# ZYNQ400-DDR.net
KiCad netlist of a schematic drawn in Altium Designer
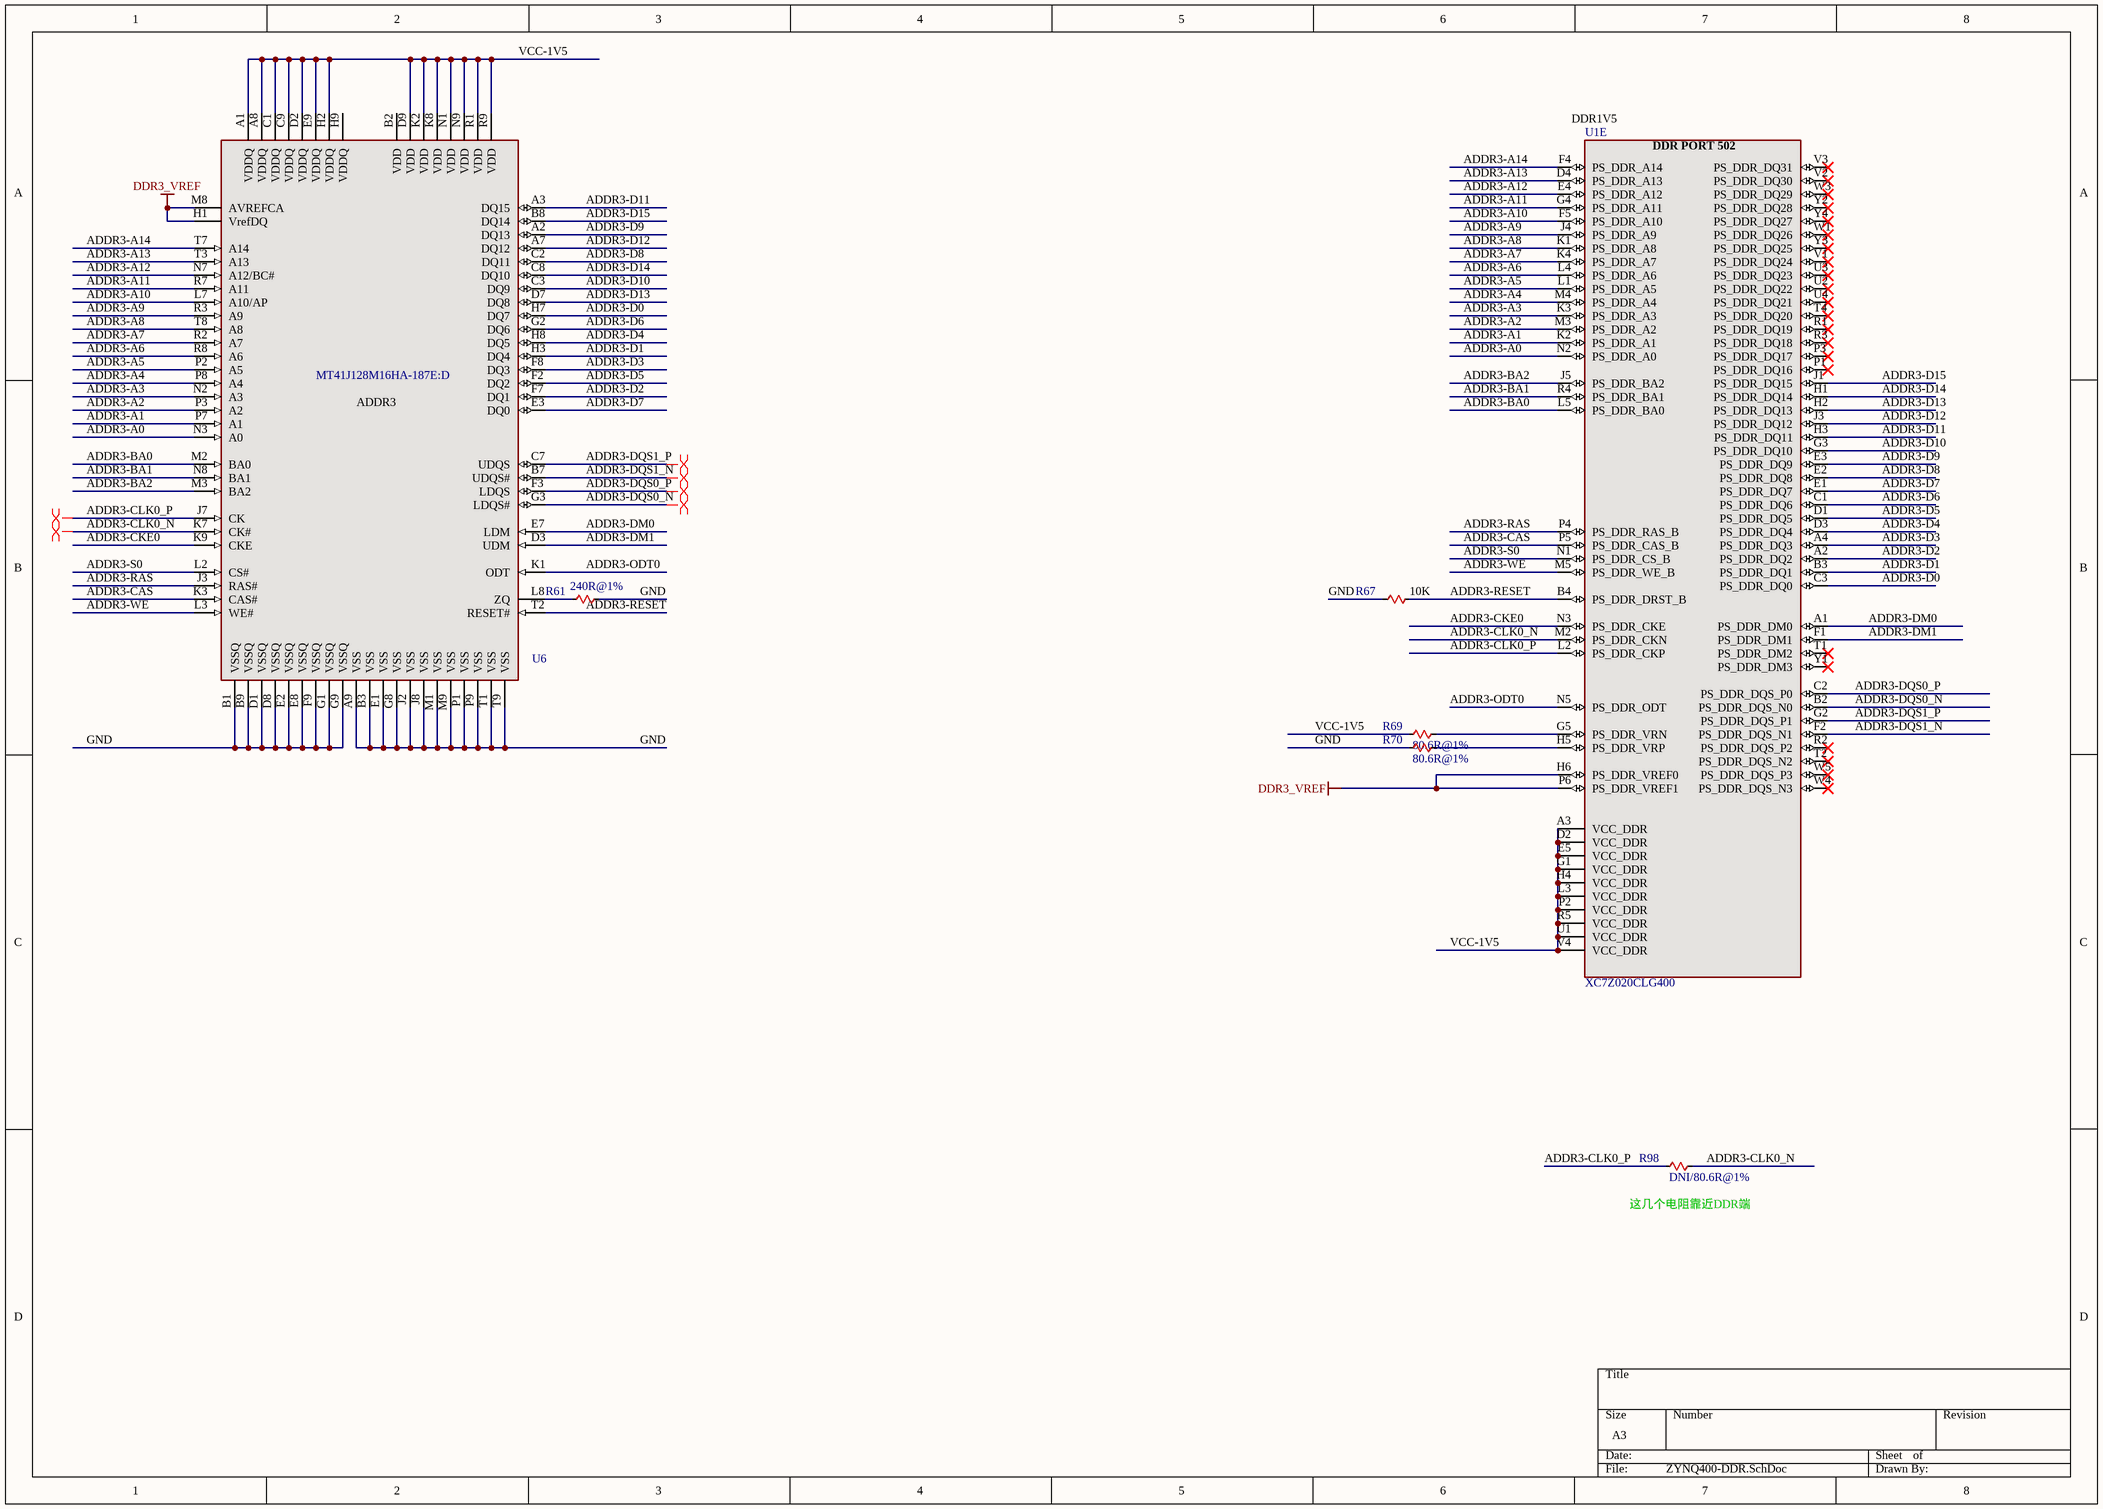
[diagram p0: ZYNQ400-DDR.SchDoc]

(export (version "E")
  (design (tool "Eeschema 10.0.6"))
  (components
    (comp (ref "R61")
      (value "240R@1%")
      (footprint "0402")
      (description "Generic Resistor")
      (libsource (lib "Digilent") (part "RESISTOR"))
    )
    (comp (ref "R67")
      (value "10K")
      (footprint "0402")
      (description "Generic Resistor")
      (libsource (lib "Digilent") (part "RESISTOR"))
    )
    (comp (ref "R69")
      (value "80.6R@1%")
      (footprint "0402")
      (description "Generic Resistor")
      (libsource (lib "Digilent") (part "RESISTOR"))
    )
    (comp (ref "R70")
      (value "80.6R@1%")
      (footprint "0402")
      (description "Generic Resistor")
      (libsource (lib "Digilent") (part "RESISTOR"))
    )
    (comp (ref "R98")
      (value "DNI/80.6R@1%")
      (footprint "0402")
      (description "Generic Resistor")
      (libsource (lib "Digilent") (part "RESISTOR"))
    )
    (comp (ref "U1")
      (value "XC7Z020CLG400")
      (footprint "CLG400")
      (description "Zynq 7000 FPGA 20 Die, in a CSG 484 Package")
      (fields (field (name "MANUFACTURER") "Xilinx"))
      (libsource (lib "gjws") (part "XC7Z020-CLG400"))
    )
    (comp (ref "U6")
      (value "MT41J128M16HA-187E:D")
      (footprint "FBGA96")
      (description "DDR3 SDRAM 2Gb x4, x8, x16")
      (fields (field (name "MANUFACTURER") "Micron"))
      (libsource (lib "Digilent") (part "MT41JxxxMxx"))
    )
  )
  (nets
    (net (code "1") (name "/ADDR3-A0") (class "Default")
      (node (ref "U1") (pin "N2") (pinfunction "PS_DDR_A0_N2") (pintype "bidirectional"))
      (node (ref "U6") (pin "N3") (pinfunction "A0_N3") (pintype "input"))
    )
    (net (code "2") (name "/ADDR3-A1") (class "Default")
      (node (ref "U1") (pin "K2") (pinfunction "PS_DDR_A1_K2") (pintype "bidirectional"))
      (node (ref "U6") (pin "P7") (pinfunction "A1_P7") (pintype "input"))
    )
    (net (code "3") (name "/ADDR3-A2") (class "Default")
      (node (ref "U1") (pin "M3") (pinfunction "PS_DDR_A2_M3") (pintype "bidirectional"))
      (node (ref "U6") (pin "P3") (pinfunction "A2_P3") (pintype "input"))
    )
    (net (code "4") (name "/ADDR3-A3") (class "Default")
      (node (ref "U1") (pin "K3") (pinfunction "PS_DDR_A3_K3") (pintype "bidirectional"))
      (node (ref "U6") (pin "N2") (pinfunction "A3_N2") (pintype "input"))
    )
    (net (code "5") (name "/ADDR3-A4") (class "Default")
      (node (ref "U1") (pin "M4") (pinfunction "PS_DDR_A4_M4") (pintype "bidirectional"))
      (node (ref "U6") (pin "P8") (pinfunction "A4_P8") (pintype "input"))
    )
    (net (code "6") (name "/ADDR3-A5") (class "Default")
      (node (ref "U1") (pin "L1") (pinfunction "PS_DDR_A5_L1") (pintype "bidirectional"))
      (node (ref "U6") (pin "P2") (pinfunction "A5_P2") (pintype "input"))
    )
    (net (code "7") (name "/ADDR3-A6") (class "Default")
      (node (ref "U1") (pin "L4") (pinfunction "PS_DDR_A6_L4") (pintype "bidirectional"))
      (node (ref "U6") (pin "R8") (pinfunction "A6_R8") (pintype "input"))
    )
    (net (code "8") (name "/ADDR3-A7") (class "Default")
      (node (ref "U1") (pin "K4") (pinfunction "PS_DDR_A7_K4") (pintype "bidirectional"))
      (node (ref "U6") (pin "R2") (pinfunction "A7_R2") (pintype "input"))
    )
    (net (code "9") (name "/ADDR3-A8") (class "Default")
      (node (ref "U1") (pin "K1") (pinfunction "PS_DDR_A8_K1") (pintype "bidirectional"))
      (node (ref "U6") (pin "T8") (pinfunction "A8_T8") (pintype "input"))
    )
    (net (code "10") (name "/ADDR3-A9") (class "Default")
      (node (ref "U1") (pin "J4") (pinfunction "PS_DDR_A9_J4") (pintype "bidirectional"))
      (node (ref "U6") (pin "R3") (pinfunction "A9_R3") (pintype "input"))
    )
    (net (code "11") (name "/ADDR3-A10") (class "Default")
      (node (ref "U1") (pin "F5") (pinfunction "PS_DDR_A10_F5") (pintype "bidirectional"))
      (node (ref "U6") (pin "L7") (pinfunction "A10/AP_L7") (pintype "input"))
    )
    (net (code "12") (name "/ADDR3-A11") (class "Default")
      (node (ref "U1") (pin "G4") (pinfunction "PS_DDR_A11_G4") (pintype "bidirectional"))
      (node (ref "U6") (pin "R7") (pinfunction "A11_R7") (pintype "input"))
    )
    (net (code "13") (name "/ADDR3-A12") (class "Default")
      (node (ref "U1") (pin "E4") (pinfunction "PS_DDR_A12_E4") (pintype "bidirectional"))
      (node (ref "U6") (pin "N7") (pinfunction "A12/BC#_N7") (pintype "input"))
    )
    (net (code "14") (name "/ADDR3-A13") (class "Default")
      (node (ref "U1") (pin "D4") (pinfunction "PS_DDR_A13_D4") (pintype "bidirectional"))
      (node (ref "U6") (pin "T3") (pinfunction "A13_T3") (pintype "input"))
    )
    (net (code "15") (name "/ADDR3-A14") (class "Default")
      (node (ref "U1") (pin "F4") (pinfunction "PS_DDR_A14_F4") (pintype "bidirectional"))
      (node (ref "U6") (pin "T7") (pinfunction "A14_T7") (pintype "input"))
    )
    (net (code "16") (name "/ADDR3-BA0") (class "Default")
      (node (ref "U1") (pin "L5") (pinfunction "PS_DDR_BA0_L5") (pintype "bidirectional"))
      (node (ref "U6") (pin "M2") (pinfunction "BA0_M2") (pintype "input"))
    )
    (net (code "17") (name "/ADDR3-BA1") (class "Default")
      (node (ref "U1") (pin "R4") (pinfunction "PS_DDR_BA1_R4") (pintype "bidirectional"))
      (node (ref "U6") (pin "N8") (pinfunction "BA1_N8") (pintype "input"))
    )
    (net (code "18") (name "/ADDR3-BA2") (class "Default")
      (node (ref "U1") (pin "J5") (pinfunction "PS_DDR_BA2_J5") (pintype "bidirectional"))
      (node (ref "U6") (pin "M3") (pinfunction "BA2_M3") (pintype "input"))
    )
    (net (code "19") (name "/ADDR3-CAS") (class "Default")
      (node (ref "U1") (pin "P5") (pinfunction "PS_DDR_CAS_B_P5") (pintype "bidirectional"))
      (node (ref "U6") (pin "K3") (pinfunction "CAS#_K3") (pintype "input"))
    )
    (net (code "20") (name "/ADDR3-CKE0") (class "Default")
      (node (ref "U1") (pin "N3") (pinfunction "PS_DDR_CKE_N3") (pintype "bidirectional"))
      (node (ref "U6") (pin "K9") (pinfunction "CKE_K9") (pintype "input"))
    )
    (net (code "21") (name "/ADDR3-CLK0_N") (class "Default")
      (node (ref "R98") (pin "2") (pinfunction "2_2") (pintype "passive"))
      (node (ref "U1") (pin "M2") (pinfunction "PS_DDR_CKN_M2") (pintype "bidirectional"))
      (node (ref "U6") (pin "K7") (pinfunction "CK#_K7") (pintype "input"))
    )
    (net (code "22") (name "/ADDR3-CLK0_P") (class "Default")
      (node (ref "R98") (pin "1") (pinfunction "1_1") (pintype "passive"))
      (node (ref "U1") (pin "L2") (pinfunction "PS_DDR_CKP_L2") (pintype "bidirectional"))
      (node (ref "U6") (pin "J7") (pinfunction "CK_J7") (pintype "input"))
    )
    (net (code "23") (name "/ADDR3-D0") (class "Default")
      (node (ref "U1") (pin "C3") (pinfunction "PS_DDR_DQ0_C3") (pintype "bidirectional"))
      (node (ref "U6") (pin "H7") (pinfunction "DQ7_H7") (pintype "bidirectional"))
    )
    (net (code "24") (name "/ADDR3-D1") (class "Default")
      (node (ref "U1") (pin "B3") (pinfunction "PS_DDR_DQ1_B3") (pintype "bidirectional"))
      (node (ref "U6") (pin "H3") (pinfunction "DQ4_H3") (pintype "bidirectional"))
    )
    (net (code "25") (name "/ADDR3-D2") (class "Default")
      (node (ref "U1") (pin "A2") (pinfunction "PS_DDR_DQ2_A2") (pintype "bidirectional"))
      (node (ref "U6") (pin "F7") (pinfunction "DQ1_F7") (pintype "bidirectional"))
    )
    (net (code "26") (name "/ADDR3-D3") (class "Default")
      (node (ref "U1") (pin "A4") (pinfunction "PS_DDR_DQ3_A4") (pintype "bidirectional"))
      (node (ref "U6") (pin "F8") (pinfunction "DQ3_F8") (pintype "bidirectional"))
    )
    (net (code "27") (name "/ADDR3-D4") (class "Default")
      (node (ref "U1") (pin "D3") (pinfunction "PS_DDR_DQ4_D3") (pintype "bidirectional"))
      (node (ref "U6") (pin "H8") (pinfunction "DQ5_H8") (pintype "bidirectional"))
    )
    (net (code "28") (name "/ADDR3-D5") (class "Default")
      (node (ref "U1") (pin "D1") (pinfunction "PS_DDR_DQ5_D1") (pintype "bidirectional"))
      (node (ref "U6") (pin "F2") (pinfunction "DQ2_F2") (pintype "bidirectional"))
    )
    (net (code "29") (name "/ADDR3-D6") (class "Default")
      (node (ref "U1") (pin "C1") (pinfunction "PS_DDR_DQ6_C1") (pintype "bidirectional"))
      (node (ref "U6") (pin "G2") (pinfunction "DQ6_G2") (pintype "bidirectional"))
    )
    (net (code "30") (name "/ADDR3-D7") (class "Default")
      (node (ref "U1") (pin "E1") (pinfunction "PS_DDR_DQ7_E1") (pintype "bidirectional"))
      (node (ref "U6") (pin "E3") (pinfunction "DQ0_E3") (pintype "bidirectional"))
    )
    (net (code "31") (name "/ADDR3-D8") (class "Default")
      (node (ref "U1") (pin "E2") (pinfunction "PS_DDR_DQ8_E2") (pintype "bidirectional"))
      (node (ref "U6") (pin "C2") (pinfunction "DQ11_C2") (pintype "bidirectional"))
    )
    (net (code "32") (name "/ADDR3-D9") (class "Default")
      (node (ref "U1") (pin "E3") (pinfunction "PS_DDR_DQ9_E3") (pintype "bidirectional"))
      (node (ref "U6") (pin "A2") (pinfunction "DQ13_A2") (pintype "bidirectional"))
    )
    (net (code "33") (name "/ADDR3-D10") (class "Default")
      (node (ref "U1") (pin "G3") (pinfunction "PS_DDR_DQ10_G3") (pintype "bidirectional"))
      (node (ref "U6") (pin "C3") (pinfunction "DQ9_C3") (pintype "bidirectional"))
    )
    (net (code "34") (name "/ADDR3-D11") (class "Default")
      (node (ref "U1") (pin "H3") (pinfunction "PS_DDR_DQ11_H3") (pintype "bidirectional"))
      (node (ref "U6") (pin "A3") (pinfunction "DQ15_A3") (pintype "bidirectional"))
    )
    (net (code "35") (name "/ADDR3-D12") (class "Default")
      (node (ref "U1") (pin "J3") (pinfunction "PS_DDR_DQ12_J3") (pintype "bidirectional"))
      (node (ref "U6") (pin "A7") (pinfunction "DQ12_A7") (pintype "bidirectional"))
    )
    (net (code "36") (name "/ADDR3-D13") (class "Default")
      (node (ref "U1") (pin "H2") (pinfunction "PS_DDR_DQ13_H2") (pintype "bidirectional"))
      (node (ref "U6") (pin "D7") (pinfunction "DQ8_D7") (pintype "bidirectional"))
    )
    (net (code "37") (name "/ADDR3-D14") (class "Default")
      (node (ref "U1") (pin "H1") (pinfunction "PS_DDR_DQ14_H1") (pintype "bidirectional"))
      (node (ref "U6") (pin "C8") (pinfunction "DQ10_C8") (pintype "bidirectional"))
    )
    (net (code "38") (name "/ADDR3-D15") (class "Default")
      (node (ref "U1") (pin "J1") (pinfunction "PS_DDR_DQ15_J1") (pintype "bidirectional"))
      (node (ref "U6") (pin "B8") (pinfunction "DQ14_B8") (pintype "bidirectional"))
    )
    (net (code "39") (name "/ADDR3-DM0") (class "Default")
      (node (ref "U1") (pin "A1") (pinfunction "PS_DDR_DM0_A1") (pintype "bidirectional"))
      (node (ref "U6") (pin "E7") (pinfunction "LDM_E7") (pintype "input"))
    )
    (net (code "40") (name "/ADDR3-DM1") (class "Default")
      (node (ref "U1") (pin "F1") (pinfunction "PS_DDR_DM1_F1") (pintype "bidirectional"))
      (node (ref "U6") (pin "D3") (pinfunction "UDM_D3") (pintype "input"))
    )
    (net (code "41") (name "/ADDR3-DQS0_N") (class "Default")
      (node (ref "U1") (pin "B2") (pinfunction "PS_DDR_DQS_N0_B2") (pintype "bidirectional"))
      (node (ref "U6") (pin "G3") (pinfunction "LDQS#_G3") (pintype "bidirectional"))
    )
    (net (code "42") (name "/ADDR3-DQS0_P") (class "Default")
      (node (ref "U1") (pin "C2") (pinfunction "PS_DDR_DQS_P0_C2") (pintype "bidirectional"))
      (node (ref "U6") (pin "F3") (pinfunction "LDQS_F3") (pintype "bidirectional"))
    )
    (net (code "43") (name "/ADDR3-DQS1_N") (class "Default")
      (node (ref "U1") (pin "F2") (pinfunction "PS_DDR_DQS_N1_F2") (pintype "bidirectional"))
      (node (ref "U6") (pin "B7") (pinfunction "UDQS#_B7") (pintype "bidirectional"))
    )
    (net (code "44") (name "/ADDR3-DQS1_P") (class "Default")
      (node (ref "U1") (pin "G2") (pinfunction "PS_DDR_DQS_P1_G2") (pintype "bidirectional"))
      (node (ref "U6") (pin "C7") (pinfunction "UDQS_C7") (pintype "bidirectional"))
    )
    (net (code "45") (name "/ADDR3-ODT0") (class "Default")
      (node (ref "U1") (pin "N5") (pinfunction "PS_DDR_ODT_N5") (pintype "bidirectional"))
      (node (ref "U6") (pin "K1") (pinfunction "ODT_K1") (pintype "input"))
    )
    (net (code "46") (name "/ADDR3-RAS") (class "Default")
      (node (ref "U1") (pin "P4") (pinfunction "PS_DDR_RAS_B_P4") (pintype "bidirectional"))
      (node (ref "U6") (pin "J3") (pinfunction "RAS#_J3") (pintype "input"))
    )
    (net (code "47") (name "/ADDR3-RESET") (class "Default")
      (node (ref "R67") (pin "1") (pinfunction "1_1") (pintype "passive"))
      (node (ref "U1") (pin "B4") (pinfunction "PS_DDR_DRST_B_B4") (pintype "bidirectional"))
      (node (ref "U6") (pin "T2") (pinfunction "RESET#_T2") (pintype "input"))
    )
    (net (code "48") (name "/ADDR3-S0") (class "Default")
      (node (ref "U1") (pin "N1") (pinfunction "PS_DDR_CS_B_N1") (pintype "bidirectional"))
      (node (ref "U6") (pin "L2") (pinfunction "CS#_L2") (pintype "input"))
    )
    (net (code "49") (name "/ADDR3-WE") (class "Default")
      (node (ref "U1") (pin "M5") (pinfunction "PS_DDR_WE_B_M5") (pintype "bidirectional"))
      (node (ref "U6") (pin "L3") (pinfunction "WE#_L3") (pintype "input"))
    )
    (net (code "50") (name "/GND") (class "Default")
      (node (ref "R61") (pin "2") (pinfunction "2_2") (pintype "passive"))
      (node (ref "R67") (pin "2") (pinfunction "2_2") (pintype "passive"))
      (node (ref "R70") (pin "1") (pinfunction "1_1") (pintype "passive"))
      (node (ref "U6") (pin "A9") (pinfunction "VSS_A9") (pintype "power_in"))
      (node (ref "U6") (pin "B1") (pinfunction "VSSQ_B1") (pintype "power_in"))
      (node (ref "U6") (pin "B3") (pinfunction "VSS_B3") (pintype "power_in"))
      (node (ref "U6") (pin "B9") (pinfunction "VSSQ_B9") (pintype "power_in"))
      (node (ref "U6") (pin "D1") (pinfunction "VSSQ_D1") (pintype "power_in"))
      (node (ref "U6") (pin "D8") (pinfunction "VSSQ_D8") (pintype "power_in"))
      (node (ref "U6") (pin "E1") (pinfunction "VSS_E1") (pintype "power_in"))
      (node (ref "U6") (pin "E2") (pinfunction "VSSQ_E2") (pintype "power_in"))
      (node (ref "U6") (pin "E8") (pinfunction "VSSQ_E8") (pintype "power_in"))
      (node (ref "U6") (pin "F9") (pinfunction "VSSQ_F9") (pintype "power_in"))
      (node (ref "U6") (pin "G1") (pinfunction "VSSQ_G1") (pintype "power_in"))
      (node (ref "U6") (pin "G8") (pinfunction "VSS_G8") (pintype "power_in"))
      (node (ref "U6") (pin "G9") (pinfunction "VSSQ_G9") (pintype "power_in"))
      (node (ref "U6") (pin "J2") (pinfunction "VSS_J2") (pintype "power_in"))
      (node (ref "U6") (pin "J8") (pinfunction "VSS_J8") (pintype "power_in"))
      (node (ref "U6") (pin "M1") (pinfunction "VSS_M1") (pintype "power_in"))
      (node (ref "U6") (pin "M9") (pinfunction "VSS_M9") (pintype "power_in"))
      (node (ref "U6") (pin "P1") (pinfunction "VSS_P1") (pintype "power_in"))
      (node (ref "U6") (pin "P9") (pinfunction "VSS_P9") (pintype "power_in"))
      (node (ref "U6") (pin "T1") (pinfunction "VSS_T1") (pintype "power_in"))
      (node (ref "U6") (pin "T9") (pinfunction "VSS_T9") (pintype "power_in"))
    )
    (net (code "51") (name "/VCC-1V5") (class "Default")
      (node (ref "R69") (pin "1") (pinfunction "1_1") (pintype "passive"))
      (node (ref "U1") (pin "A3") (pinfunction "VCC_DDR_A3") (pintype "power_in"))
      (node (ref "U1") (pin "D2") (pinfunction "VCC_DDR_D2") (pintype "power_in"))
      (node (ref "U1") (pin "E5") (pinfunction "VCC_DDR_E5") (pintype "power_in"))
      (node (ref "U1") (pin "G1") (pinfunction "VCC_DDR_G1") (pintype "power_in"))
      (node (ref "U1") (pin "H4") (pinfunction "VCC_DDR_H4") (pintype "power_in"))
      (node (ref "U1") (pin "L3") (pinfunction "VCC_DDR_L3") (pintype "power_in"))
      (node (ref "U1") (pin "P2") (pinfunction "VCC_DDR_P2") (pintype "power_in"))
      (node (ref "U1") (pin "R5") (pinfunction "VCC_DDR_R5") (pintype "power_in"))
      (node (ref "U1") (pin "U1") (pinfunction "VCC_DDR_U1") (pintype "power_in"))
      (node (ref "U1") (pin "V4") (pinfunction "VCC_DDR_V4") (pintype "power_in"))
      (node (ref "U6") (pin "A1") (pinfunction "VDDQ_A1") (pintype "power_in"))
      (node (ref "U6") (pin "A8") (pinfunction "VDDQ_A8") (pintype "power_in"))
      (node (ref "U6") (pin "C1") (pinfunction "VDDQ_C1") (pintype "power_in"))
      (node (ref "U6") (pin "C9") (pinfunction "VDDQ_C9") (pintype "power_in"))
      (node (ref "U6") (pin "D2") (pinfunction "VDDQ_D2") (pintype "power_in"))
      (node (ref "U6") (pin "D9") (pinfunction "VDD_D9") (pintype "power_in"))
      (node (ref "U6") (pin "E9") (pinfunction "VDDQ_E9") (pintype "power_in"))
      (node (ref "U6") (pin "H2") (pinfunction "VDDQ_H2") (pintype "power_in"))
      (node (ref "U6") (pin "K2") (pinfunction "VDD_K2") (pintype "power_in"))
      (node (ref "U6") (pin "K8") (pinfunction "VDD_K8") (pintype "power_in"))
      (node (ref "U6") (pin "N1") (pinfunction "VDD_N1") (pintype "power_in"))
      (node (ref "U6") (pin "N9") (pinfunction "VDD_N9") (pintype "power_in"))
      (node (ref "U6") (pin "R1") (pinfunction "VDD_R1") (pintype "power_in"))
      (node (ref "U6") (pin "R9") (pinfunction "VDD_R9") (pintype "power_in"))
    )
    (net (code "52") (name "DDR3_VREF") (class "Default")
      (node (ref "U1") (pin "H6") (pinfunction "PS_DDR_VREF0_H6") (pintype "bidirectional"))
      (node (ref "U1") (pin "P6") (pinfunction "PS_DDR_VREF1_P6") (pintype "bidirectional"))
      (node (ref "U6") (pin "H1") (pinfunction "VrefDQ_H1") (pintype "power_in"))
      (node (ref "U6") (pin "M8") (pinfunction "AVREFCA_M8") (pintype "power_in"))
    )
    (net (code "53") (name "Net-(U1E-PS_DDR_VRN)") (class "Default")
      (node (ref "R69") (pin "2") (pinfunction "2_2") (pintype "passive"))
      (node (ref "U1") (pin "G5") (pinfunction "PS_DDR_VRN_G5") (pintype "bidirectional"))
    )
    (net (code "54") (name "Net-(U1E-PS_DDR_VRP)") (class "Default")
      (node (ref "R70") (pin "2") (pinfunction "2_2") (pintype "passive"))
      (node (ref "U1") (pin "H5") (pinfunction "PS_DDR_VRP_H5") (pintype "bidirectional"))
    )
    (net (code "55") (name "Net-(U6-ZQ)") (class "Default")
      (node (ref "R61") (pin "1") (pinfunction "1_1") (pintype "passive"))
      (node (ref "U6") (pin "L8") (pinfunction "ZQ_L8") (pintype "passive"))
    )
    (net (code "56") (name "unconnected-(U1E-PS_DDR_DM2-PadT1)") (class "Default")
      (node (ref "U1") (pin "T1") (pinfunction "PS_DDR_DM2_T1") (pintype "bidirectional+no_connect"))
    )
    (net (code "57") (name "unconnected-(U1E-PS_DDR_DM3-PadY1)") (class "Default")
      (node (ref "U1") (pin "Y1") (pinfunction "PS_DDR_DM3_Y1") (pintype "bidirectional+no_connect"))
    )
    (net (code "58") (name "unconnected-(U1E-PS_DDR_DQ16-PadP1)") (class "Default")
      (node (ref "U1") (pin "P1") (pinfunction "PS_DDR_DQ16_P1") (pintype "bidirectional+no_connect"))
    )
    (net (code "59") (name "unconnected-(U1E-PS_DDR_DQ17-PadP3)") (class "Default")
      (node (ref "U1") (pin "P3") (pinfunction "PS_DDR_DQ17_P3") (pintype "bidirectional+no_connect"))
    )
    (net (code "60") (name "unconnected-(U1E-PS_DDR_DQ18-PadR3)") (class "Default")
      (node (ref "U1") (pin "R3") (pinfunction "PS_DDR_DQ18_R3") (pintype "bidirectional+no_connect"))
    )
    (net (code "61") (name "unconnected-(U1E-PS_DDR_DQ19-PadR1)") (class "Default")
      (node (ref "U1") (pin "R1") (pinfunction "PS_DDR_DQ19_R1") (pintype "bidirectional+no_connect"))
    )
    (net (code "62") (name "unconnected-(U1E-PS_DDR_DQ20-PadT4)") (class "Default")
      (node (ref "U1") (pin "T4") (pinfunction "PS_DDR_DQ20_T4") (pintype "bidirectional+no_connect"))
    )
    (net (code "63") (name "unconnected-(U1E-PS_DDR_DQ21-PadU4)") (class "Default")
      (node (ref "U1") (pin "U4") (pinfunction "PS_DDR_DQ21_U4") (pintype "bidirectional+no_connect"))
    )
    (net (code "64") (name "unconnected-(U1E-PS_DDR_DQ22-PadU2)") (class "Default")
      (node (ref "U1") (pin "U2") (pinfunction "PS_DDR_DQ22_U2") (pintype "bidirectional+no_connect"))
    )
    (net (code "65") (name "unconnected-(U1E-PS_DDR_DQ23-PadU3)") (class "Default")
      (node (ref "U1") (pin "U3") (pinfunction "PS_DDR_DQ23_U3") (pintype "bidirectional+no_connect"))
    )
    (net (code "66") (name "unconnected-(U1E-PS_DDR_DQ24-PadV1)") (class "Default")
      (node (ref "U1") (pin "V1") (pinfunction "PS_DDR_DQ24_V1") (pintype "bidirectional+no_connect"))
    )
    (net (code "67") (name "unconnected-(U1E-PS_DDR_DQ25-PadY3)") (class "Default")
      (node (ref "U1") (pin "Y3") (pinfunction "PS_DDR_DQ25_Y3") (pintype "bidirectional+no_connect"))
    )
    (net (code "68") (name "unconnected-(U1E-PS_DDR_DQ26-PadW1)") (class "Default")
      (node (ref "U1") (pin "W1") (pinfunction "PS_DDR_DQ26_W1") (pintype "bidirectional+no_connect"))
    )
    (net (code "69") (name "unconnected-(U1E-PS_DDR_DQ27-PadY4)") (class "Default")
      (node (ref "U1") (pin "Y4") (pinfunction "PS_DDR_DQ27_Y4") (pintype "bidirectional+no_connect"))
    )
    (net (code "70") (name "unconnected-(U1E-PS_DDR_DQ28-PadY2)") (class "Default")
      (node (ref "U1") (pin "Y2") (pinfunction "PS_DDR_DQ28_Y2") (pintype "bidirectional+no_connect"))
    )
    (net (code "71") (name "unconnected-(U1E-PS_DDR_DQ29-PadW3)") (class "Default")
      (node (ref "U1") (pin "W3") (pinfunction "PS_DDR_DQ29_W3") (pintype "bidirectional+no_connect"))
    )
    (net (code "72") (name "unconnected-(U1E-PS_DDR_DQ30-PadV2)") (class "Default")
      (node (ref "U1") (pin "V2") (pinfunction "PS_DDR_DQ30_V2") (pintype "bidirectional+no_connect"))
    )
    (net (code "73") (name "unconnected-(U1E-PS_DDR_DQ31-PadV3)") (class "Default")
      (node (ref "U1") (pin "V3") (pinfunction "PS_DDR_DQ31_V3") (pintype "bidirectional+no_connect"))
    )
    (net (code "74") (name "unconnected-(U1E-PS_DDR_DQS_N2-PadT2)") (class "Default")
      (node (ref "U1") (pin "T2") (pinfunction "PS_DDR_DQS_N2_T2") (pintype "bidirectional+no_connect"))
    )
    (net (code "75") (name "unconnected-(U1E-PS_DDR_DQS_N3-PadW4)") (class "Default")
      (node (ref "U1") (pin "W4") (pinfunction "PS_DDR_DQS_N3_W4") (pintype "bidirectional+no_connect"))
    )
    (net (code "76") (name "unconnected-(U1E-PS_DDR_DQS_P2-PadR2)") (class "Default")
      (node (ref "U1") (pin "R2") (pinfunction "PS_DDR_DQS_P2_R2") (pintype "bidirectional+no_connect"))
    )
    (net (code "77") (name "unconnected-(U1E-PS_DDR_DQS_P3-PadW5)") (class "Default")
      (node (ref "U1") (pin "W5") (pinfunction "PS_DDR_DQS_P3_W5") (pintype "bidirectional+no_connect"))
    )
    (net (code "78") (name "unconnected-(U6-VDD-PadB2)") (class "Default")
      (node (ref "U6") (pin "B2") (pinfunction "VDD_B2") (pintype "power_in"))
    )
    (net (code "79") (name "unconnected-(U6-VDDQ-PadH9)") (class "Default")
      (node (ref "U6") (pin "H9") (pinfunction "VDDQ_H9") (pintype "power_in"))
    )
  )
)
